# I2C_EXPANDER.net
KiCad netlist of a schematic drawn in Altium Designer
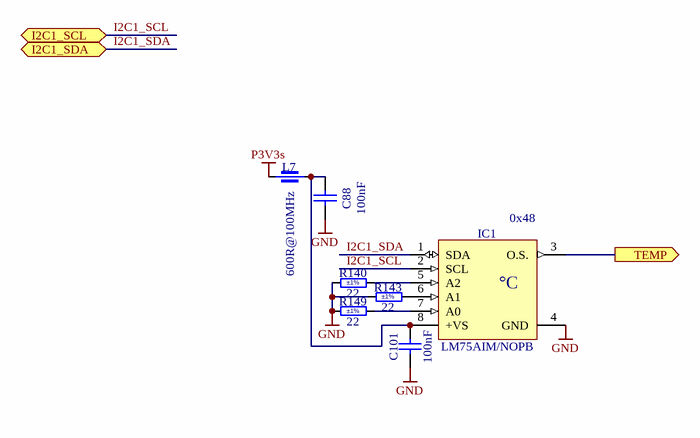
[diagram p0: I2C_EXPANDER.SchDoc]

(export (version "E")
  (design (tool "Eeschema 10.0.6"))
  (components
    (comp (ref "C88")
      (value "100nF")
      (footprint "CAPC1608X87N")
      (description "Non-polarised capacitor")
      (fields
        (field (name "PART NUMBER") "CC0603_100NF_50V_10%_X7R")
        (field (name "VOLTAGE") "50V")
        (field (name "AUTHOR") "CERN DEM JLC")
      )
      (libsource (lib "Capacitors") (part "Capacitor - non polarized"))
    )
    (comp (ref "C101")
      (value "100nF")
      (footprint "CAPC1608X87N")
      (description "Non-polarised capacitor")
      (fields
        (field (name "PART NUMBER") "CC0603_100NF_50V_10%_X7R")
        (field (name "VOLTAGE") "50V")
        (field (name "AUTHOR") "CERN DEM JLC")
      )
      (libsource (lib "Capacitors") (part "Capacitor - non polarized"))
    )
    (comp (ref "IC1")
      (value "LM75AIM/NOPB")
      (footprint "SOIC127P600X175-8N")
      (description "Digital Temperature Sensor and Thermal Watchdog with Two-Wire Interface")
      (fields (field (name "MANUFACTURER") "TEXAS INSTRUMENTS") (field (name "AUTHOR") "CERN DEM JLC"))
      (libsource (lib "ICs And Semiconductors") (part "LM75"))
    )
    (comp (ref "L7")
      (value "600R@100MHz")
      (footprint "INDC1608X95N")
      (fields
        (field (name "PART NUMBER") "IND0603_MURATA_BLM18AG601SN1")
        (field (name "POWER") "500mA")
        (field (name "TOLERANCE") "±25%")
        (field (name "AUTHOR") "CERN DEM MR")
      )
      (libsource (lib "Inductors & Transformers") (part "Ferrite Bead"))
    )
    (comp (ref "R140")
      (value "22")
      (footprint "RESC1608X55N")
      (description "Resistor - 1%")
      (fields
        (field (name "TOLERANCE") "±1%")
        (field (name "PART NUMBER") "R0603_22R_1%_0.1W_100PPM")
        (field (name "POWER") "0.1W")
        (field (name "AUTHOR") "CERN DEM JLC")
      )
      (libsource (lib "Resistors") (part "Resistor - 1%"))
    )
    (comp (ref "R143")
      (value "22")
      (footprint "RESC1608X55N")
      (description "Resistor - 1%")
      (fields
        (field (name "TOLERANCE") "±1%")
        (field (name "PART NUMBER") "R0603_22R_1%_0.1W_100PPM")
        (field (name "POWER") "0.1W")
        (field (name "AUTHOR") "CERN DEM JLC")
      )
      (libsource (lib "Resistors") (part "Resistor - 1%"))
    )
    (comp (ref "R149")
      (value "22")
      (footprint "RESC1608X55N")
      (description "Resistor - 1%")
      (fields
        (field (name "TOLERANCE") "±1%")
        (field (name "PART NUMBER") "R0603_22R_1%_0.1W_100PPM")
        (field (name "POWER") "0.1W")
        (field (name "AUTHOR") "CERN DEM JLC")
      )
      (libsource (lib "Resistors") (part "Resistor - 1%"))
    )
  )
  (nets
    (net (code "1") (name "/I2C1_SCL") (class "Default")
      (node (ref "IC1") (pin "2") (pinfunction "SCL_2") (pintype "input"))
    )
    (net (code "2") (name "/I2C1_SDA") (class "Default")
      (node (ref "IC1") (pin "1") (pinfunction "SDA_1") (pintype "bidirectional"))
    )
    (net (code "3") (name "/TEMP") (class "Default")
      (node (ref "IC1") (pin "3") (pinfunction "O.S._3") (pintype "output"))
    )
    (net (code "4") (name "GND") (class "Default")
      (node (ref "C101") (pin "1") (pinfunction "1_1") (pintype "passive"))
      (node (ref "C88") (pin "1") (pinfunction "1_1") (pintype "passive"))
      (node (ref "IC1") (pin "4") (pinfunction "GND_4") (pintype "power_in"))
      (node (ref "R140") (pin "1") (pinfunction "1_1") (pintype "passive"))
      (node (ref "R143") (pin "1") (pinfunction "1_1") (pintype "passive"))
      (node (ref "R149") (pin "1") (pinfunction "1_1") (pintype "passive"))
    )
    (net (code "5") (name "Net-(IC1-+VS)") (class "Default")
      (node (ref "C101") (pin "2") (pinfunction "2_2") (pintype "passive"))
      (node (ref "C88") (pin "2") (pinfunction "2_2") (pintype "passive"))
      (node (ref "IC1") (pin "8") (pinfunction "+VS_8") (pintype "power_in"))
      (node (ref "L7") (pin "2") (pinfunction "2_2") (pintype "passive"))
    )
    (net (code "6") (name "Net-(IC1-A0)") (class "Default")
      (node (ref "IC1") (pin "7") (pinfunction "A0_7") (pintype "input"))
      (node (ref "R149") (pin "2") (pinfunction "2_2") (pintype "passive"))
    )
    (net (code "7") (name "Net-(IC1-A1)") (class "Default")
      (node (ref "IC1") (pin "6") (pinfunction "A1_6") (pintype "input"))
      (node (ref "R143") (pin "2") (pinfunction "2_2") (pintype "passive"))
    )
    (net (code "8") (name "Net-(IC1-A2)") (class "Default")
      (node (ref "IC1") (pin "5") (pinfunction "A2_5") (pintype "input"))
      (node (ref "R140") (pin "2") (pinfunction "2_2") (pintype "passive"))
    )
    (net (code "9") (name "P3V3s") (class "Default")
      (node (ref "L7") (pin "1") (pinfunction "1_1") (pintype "passive"))
    )
  )
)
